# Power.net
KiCad netlist of a schematic drawn in Altium Designer
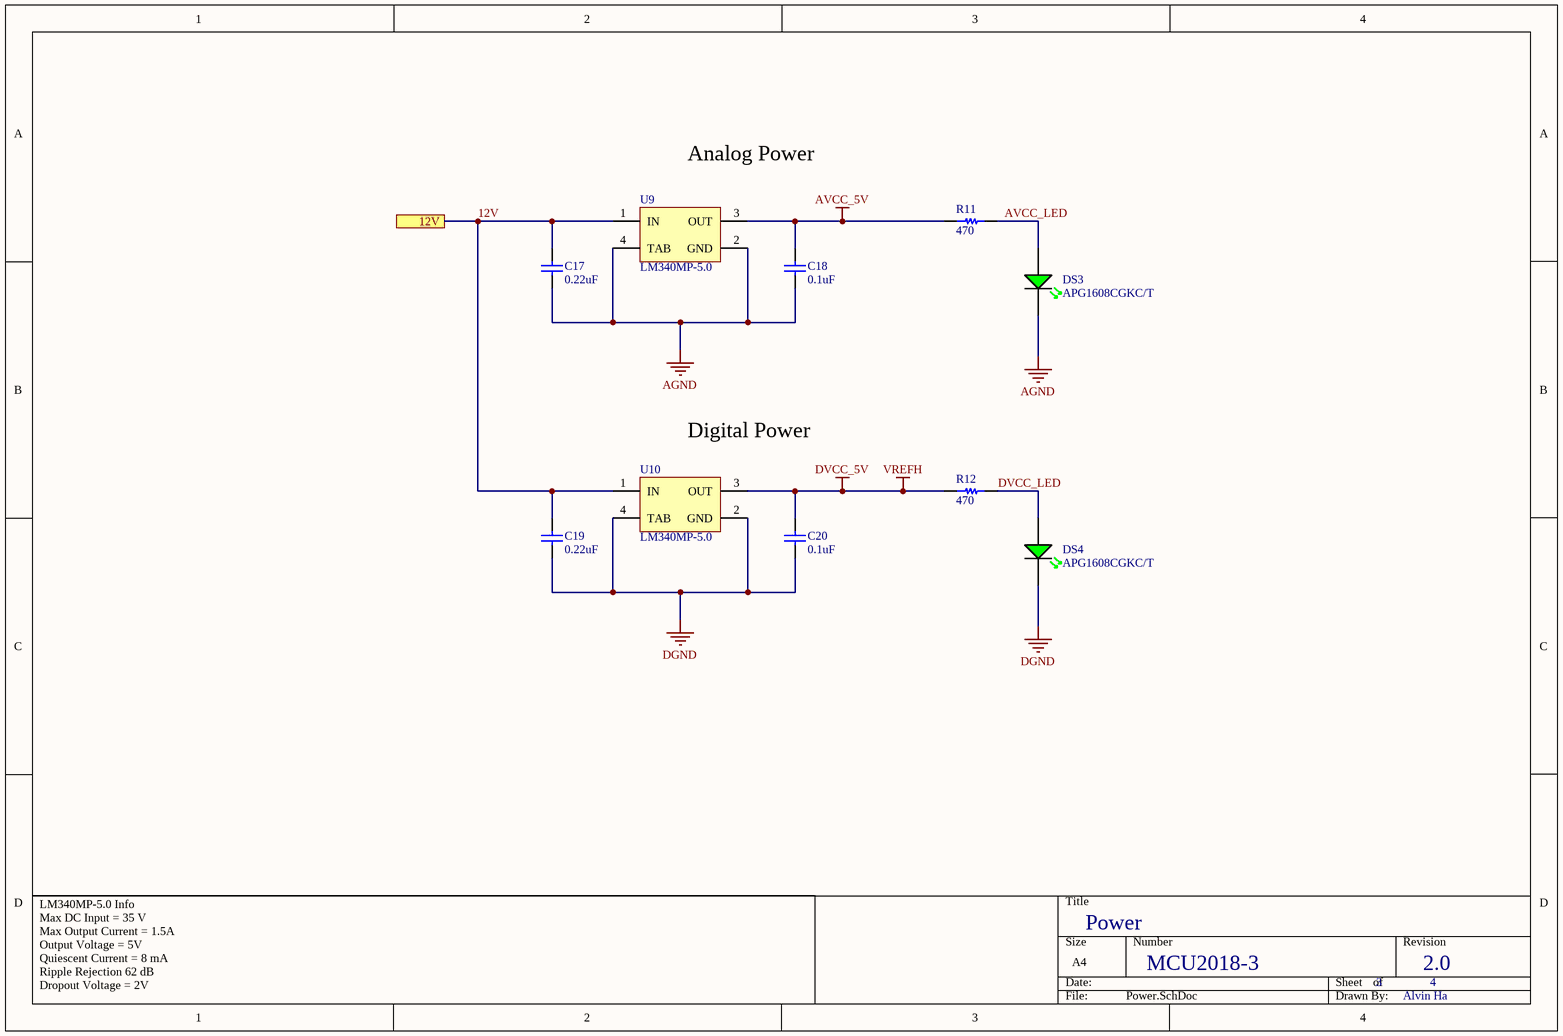
[diagram p0: Power.SchDoc]

(export (version "E")
  (design (tool "Eeschema 10.0.6"))
  (components
    (comp (ref "C17")
      (value "0.22uF")
      (footprint "CAP SMT 0603")
      (libsource (lib "Components") (part "Capacitor 0.22uF 25V 0603"))
    )
    (comp (ref "C18")
      (value "0.1uF")
      (footprint "CAP SMT 0603")
      (libsource (lib "Components") (part "Capacitor 0.1uF 25V 0603"))
    )
    (comp (ref "C19")
      (value "0.22uF")
      (footprint "CAP SMT 0603")
      (libsource (lib "Components") (part "Capacitor 0.22uF 25V 0603"))
    )
    (comp (ref "C20")
      (value "0.1uF")
      (footprint "CAP SMT 0603")
      (libsource (lib "Components") (part "Capacitor 0.1uF 25V 0603"))
    )
    (comp (ref "DS3")
      (value "APG1608CGKC/T")
      (footprint "GREEN LED")
      (libsource (lib "CPRacingUnifiedLibrary") (part "Green LED"))
    )
    (comp (ref "DS4")
      (value "APG1608CGKC/T")
      (footprint "GREEN LED")
      (libsource (lib "CPRacingUnifiedLibrary") (part "Green LED"))
    )
    (comp (ref "R11")
      (value "470")
      (footprint "RES SMT 0805")
      (libsource (lib "Components") (part "Resistor 470 1% 0805"))
    )
    (comp (ref "R12")
      (value "470")
      (footprint "RES SMT 0805")
      (libsource (lib "Components") (part "Resistor 470 1% 0805"))
    )
    (comp (ref "U9")
      (value "LM340MP-5.0")
      (footprint "DCY0004A_M")
      (description "Series 3-Terminal Positive Regulators, 4-pin SOT-223")
      (fields (field (name "MANUFACTURER") "Texas Instruments"))
      (libsource (lib "Altium Content Vault") (part "PM-REG-LM2940-TO4"))
    )
    (comp (ref "U10")
      (value "LM340MP-5.0")
      (footprint "DCY0004A_M")
      (description "Series 3-Terminal Positive Regulators, 4-pin SOT-223")
      (fields (field (name "MANUFACTURER") "Texas Instruments"))
      (libsource (lib "Altium Content Vault") (part "PM-REG-LM2940-TO4"))
    )
  )
  (nets
    (net (code "1") (name "/12V") (class "Default")
      (node (ref "C17") (pin "2") (pinfunction "2_2") (pintype "passive"))
      (node (ref "C19") (pin "2") (pinfunction "2_2") (pintype "passive"))
      (node (ref "U10") (pin "1") (pinfunction "IN_1") (pintype "power_in"))
      (node (ref "U9") (pin "1") (pinfunction "IN_1") (pintype "power_in"))
    )
    (net (code "2") (name "/AVCC_LED") (class "Default")
      (node (ref "DS3") (pin "2") (pinfunction "2_2") (pintype "passive"))
      (node (ref "R11") (pin "2") (pinfunction "2_2") (pintype "passive"))
    )
    (net (code "3") (name "/DVCC_LED") (class "Default")
      (node (ref "DS4") (pin "2") (pinfunction "2_2") (pintype "passive"))
      (node (ref "R12") (pin "2") (pinfunction "2_2") (pintype "passive"))
    )
    (net (code "4") (name "AGND") (class "Default")
      (node (ref "C17") (pin "1") (pinfunction "1_1") (pintype "passive"))
      (node (ref "C18") (pin "1") (pinfunction "1_1") (pintype "passive"))
      (node (ref "DS3") (pin "1") (pinfunction "1_1") (pintype "passive"))
      (node (ref "U9") (pin "2") (pinfunction "GND_2") (pintype "power_in"))
      (node (ref "U9") (pin "4") (pinfunction "TAB_4") (pintype "power_in"))
    )
    (net (code "5") (name "AVCC_5V") (class "Default")
      (node (ref "C18") (pin "2") (pinfunction "2_2") (pintype "passive"))
      (node (ref "R11") (pin "1") (pinfunction "1_1") (pintype "passive"))
      (node (ref "U9") (pin "3") (pinfunction "OUT_3") (pintype "power_in"))
    )
    (net (code "6") (name "DGND") (class "Default")
      (node (ref "C19") (pin "1") (pinfunction "1_1") (pintype "passive"))
      (node (ref "C20") (pin "1") (pinfunction "1_1") (pintype "passive"))
      (node (ref "DS4") (pin "1") (pinfunction "1_1") (pintype "passive"))
      (node (ref "U10") (pin "2") (pinfunction "GND_2") (pintype "power_in"))
      (node (ref "U10") (pin "4") (pinfunction "TAB_4") (pintype "power_in"))
    )
    (net (code "7") (name "DVCC_5V") (class "Default")
      (node (ref "C20") (pin "2") (pinfunction "2_2") (pintype "passive"))
      (node (ref "R12") (pin "1") (pinfunction "1_1") (pintype "passive"))
      (node (ref "U10") (pin "3") (pinfunction "OUT_3") (pintype "power_in"))
    )
  )
)
